# ConnectorPMOD.net
KiCad netlist of a schematic drawn in Altium Designer
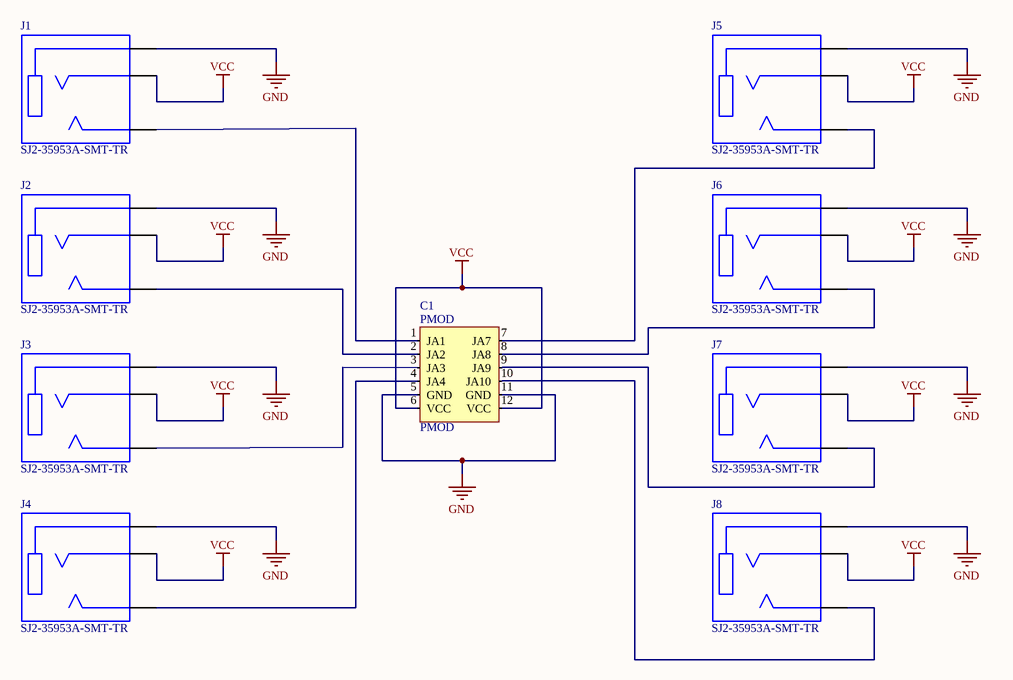
[diagram p0: ConnectorPMOD.SchDoc]

(export (version "E")
  (design (tool "Eeschema 10.0.6"))
  (components
    (comp (ref "C1") (value "PMOD") (footprint "PMOD") (libsource (lib "PMOD") (part "PMOD")))
    (comp (ref "J1")
      (value "SJ2-35953A-SMT-TR")
      (footprint "CUI_SJ2-35953A-SMT-TR")
      (description "3.5 mm, Stereo, Right Angle, Surface Mount _SMT_, Audio Jack Connector")
      (fields (field (name "MF") "CUI Devices"))
      (libsource (lib "SJ2-35953A-SMT-TR") (part "SJ2-35953A-SMT-TR"))
    )
    (comp (ref "J2")
      (value "SJ2-35953A-SMT-TR")
      (footprint "CUI_SJ2-35953A-SMT-TR")
      (description "3.5 mm, Stereo, Right Angle, Surface Mount _SMT_, Audio Jack Connector")
      (fields (field (name "MF") "CUI Devices"))
      (libsource (lib "SJ2-35953A-SMT-TR") (part "SJ2-35953A-SMT-TR"))
    )
    (comp (ref "J3")
      (value "SJ2-35953A-SMT-TR")
      (footprint "CUI_SJ2-35953A-SMT-TR")
      (description "3.5 mm, Stereo, Right Angle, Surface Mount _SMT_, Audio Jack Connector")
      (fields (field (name "MF") "CUI Devices"))
      (libsource (lib "SJ2-35953A-SMT-TR") (part "SJ2-35953A-SMT-TR"))
    )
    (comp (ref "J4")
      (value "SJ2-35953A-SMT-TR")
      (footprint "CUI_SJ2-35953A-SMT-TR")
      (description "3.5 mm, Stereo, Right Angle, Surface Mount _SMT_, Audio Jack Connector")
      (fields (field (name "MF") "CUI Devices"))
      (libsource (lib "SJ2-35953A-SMT-TR") (part "SJ2-35953A-SMT-TR"))
    )
    (comp (ref "J5")
      (value "SJ2-35953A-SMT-TR")
      (footprint "CUI_SJ2-35953A-SMT-TR")
      (description "3.5 mm, Stereo, Right Angle, Surface Mount _SMT_, Audio Jack Connector")
      (fields (field (name "MF") "CUI Devices"))
      (libsource (lib "SJ2-35953A-SMT-TR") (part "SJ2-35953A-SMT-TR"))
    )
    (comp (ref "J6")
      (value "SJ2-35953A-SMT-TR")
      (footprint "CUI_SJ2-35953A-SMT-TR")
      (description "3.5 mm, Stereo, Right Angle, Surface Mount _SMT_, Audio Jack Connector")
      (fields (field (name "MF") "CUI Devices"))
      (libsource (lib "SJ2-35953A-SMT-TR") (part "SJ2-35953A-SMT-TR"))
    )
    (comp (ref "J7")
      (value "SJ2-35953A-SMT-TR")
      (footprint "CUI_SJ2-35953A-SMT-TR")
      (description "3.5 mm, Stereo, Right Angle, Surface Mount _SMT_, Audio Jack Connector")
      (fields (field (name "MF") "CUI Devices"))
      (libsource (lib "SJ2-35953A-SMT-TR") (part "SJ2-35953A-SMT-TR"))
    )
    (comp (ref "J8")
      (value "SJ2-35953A-SMT-TR")
      (footprint "CUI_SJ2-35953A-SMT-TR")
      (description "3.5 mm, Stereo, Right Angle, Surface Mount _SMT_, Audio Jack Connector")
      (fields (field (name "MF") "CUI Devices"))
      (libsource (lib "SJ2-35953A-SMT-TR") (part "SJ2-35953A-SMT-TR"))
    )
  )
  (nets
    (net (code "1") (name "GND") (class "Default")
      (node (ref "C1") (pin "11") (pinfunction "GND_11") (pintype "power_in"))
      (node (ref "C1") (pin "5") (pinfunction "GND_5") (pintype "power_in"))
      (node (ref "J1") (pin "1") (pinfunction "SLEEVE_1") (pintype "passive"))
      (node (ref "J2") (pin "1") (pinfunction "SLEEVE_1") (pintype "passive"))
      (node (ref "J3") (pin "1") (pinfunction "SLEEVE_1") (pintype "passive"))
      (node (ref "J4") (pin "1") (pinfunction "SLEEVE_1") (pintype "passive"))
      (node (ref "J5") (pin "1") (pinfunction "SLEEVE_1") (pintype "passive"))
      (node (ref "J6") (pin "1") (pinfunction "SLEEVE_1") (pintype "passive"))
      (node (ref "J7") (pin "1") (pinfunction "SLEEVE_1") (pintype "passive"))
      (node (ref "J8") (pin "1") (pinfunction "SLEEVE_1") (pintype "passive"))
    )
    (net (code "2") (name "Net-(C1-JA1)") (class "Default")
      (node (ref "C1") (pin "1") (pinfunction "JA1_1") (pintype "output"))
      (node (ref "J1") (pin "2") (pinfunction "TIP_2") (pintype "passive"))
    )
    (net (code "3") (name "Net-(C1-JA2)") (class "Default")
      (node (ref "C1") (pin "2") (pinfunction "JA2_2") (pintype "output"))
      (node (ref "J2") (pin "2") (pinfunction "TIP_2") (pintype "passive"))
    )
    (net (code "4") (name "Net-(C1-JA3)") (class "Default")
      (node (ref "C1") (pin "3") (pinfunction "JA3_3") (pintype "output"))
      (node (ref "J3") (pin "2") (pinfunction "TIP_2") (pintype "passive"))
    )
    (net (code "5") (name "Net-(C1-JA4)") (class "Default")
      (node (ref "C1") (pin "4") (pinfunction "JA4_4") (pintype "output"))
      (node (ref "J4") (pin "2") (pinfunction "TIP_2") (pintype "passive"))
    )
    (net (code "6") (name "Net-(C1-JA7)") (class "Default")
      (node (ref "C1") (pin "7") (pinfunction "JA7_7") (pintype "output"))
      (node (ref "J5") (pin "2") (pinfunction "TIP_2") (pintype "passive"))
    )
    (net (code "7") (name "Net-(C1-JA8)") (class "Default")
      (node (ref "C1") (pin "8") (pinfunction "JA8_8") (pintype "output"))
      (node (ref "J6") (pin "2") (pinfunction "TIP_2") (pintype "passive"))
    )
    (net (code "8") (name "Net-(C1-JA9)") (class "Default")
      (node (ref "C1") (pin "9") (pinfunction "JA9_9") (pintype "output"))
      (node (ref "J7") (pin "2") (pinfunction "TIP_2") (pintype "passive"))
    )
    (net (code "9") (name "Net-(C1-JA10)") (class "Default")
      (node (ref "C1") (pin "10") (pinfunction "JA10_10") (pintype "output"))
      (node (ref "J8") (pin "2") (pinfunction "TIP_2") (pintype "passive"))
    )
    (net (code "10") (name "VCC") (class "Default")
      (node (ref "C1") (pin "12") (pinfunction "VCC_12") (pintype "power_in"))
      (node (ref "C1") (pin "6") (pinfunction "VCC_6") (pintype "power_in"))
      (node (ref "J1") (pin "3") (pinfunction "RING1_3") (pintype "passive"))
      (node (ref "J2") (pin "3") (pinfunction "RING1_3") (pintype "passive"))
      (node (ref "J3") (pin "3") (pinfunction "RING1_3") (pintype "passive"))
      (node (ref "J4") (pin "3") (pinfunction "RING1_3") (pintype "passive"))
      (node (ref "J5") (pin "3") (pinfunction "RING1_3") (pintype "passive"))
      (node (ref "J6") (pin "3") (pinfunction "RING1_3") (pintype "passive"))
      (node (ref "J7") (pin "3") (pinfunction "RING1_3") (pintype "passive"))
      (node (ref "J8") (pin "3") (pinfunction "RING1_3") (pintype "passive"))
    )
  )
)
